# PGTNX05_mainboard.net
KiCad netlist of a schematic drawn in EAGLE
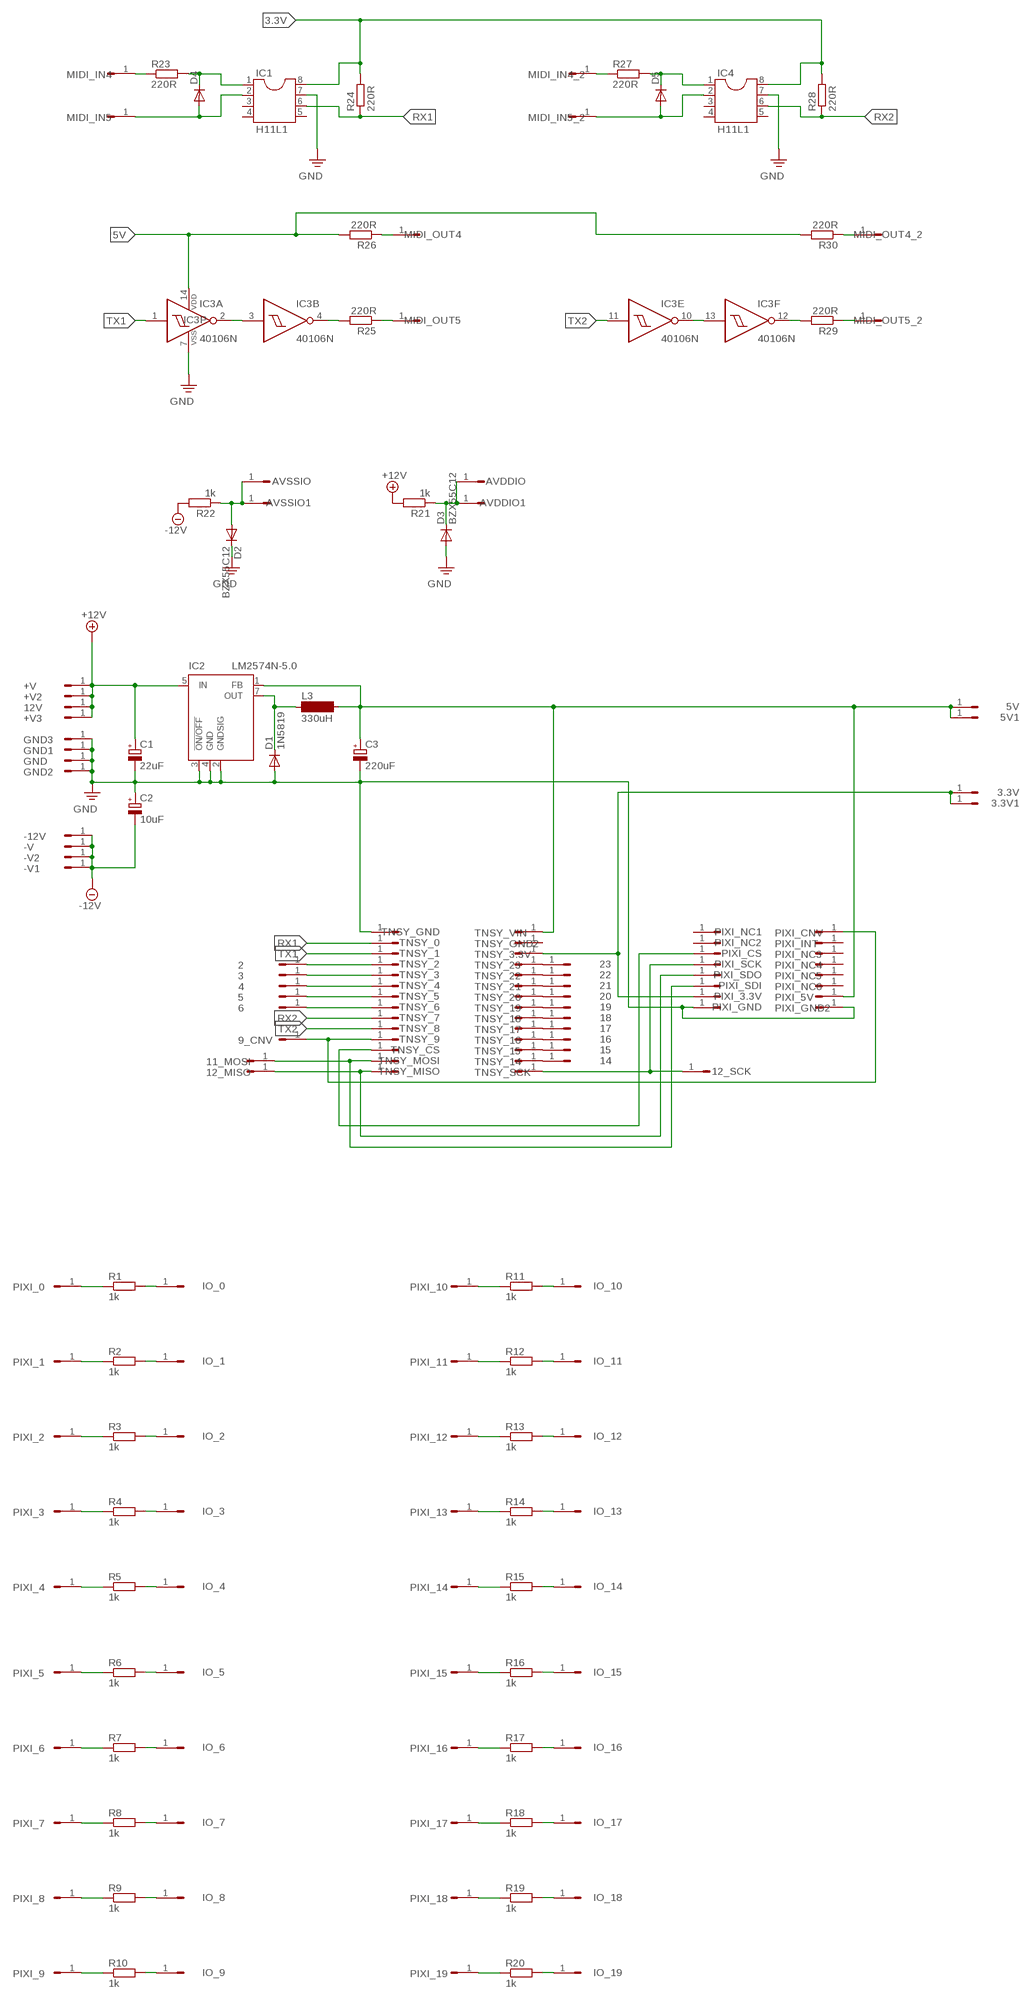
[diagram p0: schematic, sheet 1]

(export (version "E")
  (design (tool "Eeschema 10.0.6"))
  (components
    (comp (ref "+V")
      (value "HEADER/MALE/01")
      (footprint "eagle-import:HEADER_MALE_01")
      (fields (field (name "SPICEPREFIX") "X"))
      (libsource (lib "eagle-import") (part "HEADER/MALE/01"))
    )
    (comp (ref "+V2")
      (value "HEADER/MALE/01")
      (footprint "eagle-import:HEADER_MALE_01")
      (fields (field (name "SPICEPREFIX") "X"))
      (libsource (lib "eagle-import") (part "HEADER/MALE/01"))
    )
    (comp (ref "+V3")
      (value "HEADER/MALE/01")
      (footprint "eagle-import:HEADER_MALE_01")
      (fields (field (name "SPICEPREFIX") "X"))
      (libsource (lib "eagle-import") (part "HEADER/MALE/01"))
    )
    (comp (ref "-12V")
      (value "HEADER/MALE/01")
      (footprint "eagle-import:HEADER_MALE_01")
      (fields (field (name "SPICEPREFIX") "X"))
      (libsource (lib "eagle-import") (part "HEADER/MALE/01"))
    )
    (comp (ref "-V")
      (value "HEADER/MALE/01")
      (footprint "eagle-import:HEADER_MALE_01")
      (fields (field (name "SPICEPREFIX") "X"))
      (libsource (lib "eagle-import") (part "HEADER/MALE/01"))
    )
    (comp (ref "-V1")
      (value "HEADER/MALE/01")
      (footprint "eagle-import:HEADER_MALE_01")
      (fields (field (name "SPICEPREFIX") "X"))
      (libsource (lib "eagle-import") (part "HEADER/MALE/01"))
    )
    (comp (ref "-V2")
      (value "HEADER/MALE/01")
      (footprint "eagle-import:HEADER_MALE_01")
      (fields (field (name "SPICEPREFIX") "X"))
      (libsource (lib "eagle-import") (part "HEADER/MALE/01"))
    )
    (comp (ref "2")
      (value "HEADER/MALE/01")
      (footprint "eagle-import:HEADER_MALE_01")
      (fields (field (name "SPICEPREFIX") "X"))
      (libsource (lib "eagle-import") (part "HEADER/MALE/01"))
    )
    (comp (ref "3")
      (value "HEADER/MALE/01")
      (footprint "eagle-import:HEADER_MALE_01")
      (fields (field (name "SPICEPREFIX") "X"))
      (libsource (lib "eagle-import") (part "HEADER/MALE/01"))
    )
    (comp (ref "3.3V")
      (value "HEADER/MALE/01")
      (footprint "eagle-import:HEADER_MALE_01")
      (fields (field (name "SPICEPREFIX") "X"))
      (libsource (lib "eagle-import") (part "HEADER/MALE/01"))
    )
    (comp (ref "3.3V1")
      (value "HEADER/MALE/01")
      (footprint "eagle-import:HEADER_MALE_01")
      (fields (field (name "SPICEPREFIX") "X"))
      (libsource (lib "eagle-import") (part "HEADER/MALE/01"))
    )
    (comp (ref "4")
      (value "HEADER/MALE/01")
      (footprint "eagle-import:HEADER_MALE_01")
      (fields (field (name "SPICEPREFIX") "X"))
      (libsource (lib "eagle-import") (part "HEADER/MALE/01"))
    )
    (comp (ref "5")
      (value "HEADER/MALE/01")
      (footprint "eagle-import:HEADER_MALE_01")
      (fields (field (name "SPICEPREFIX") "X"))
      (libsource (lib "eagle-import") (part "HEADER/MALE/01"))
    )
    (comp (ref "5V")
      (value "HEADER/MALE/01")
      (footprint "eagle-import:HEADER_MALE_01")
      (fields (field (name "SPICEPREFIX") "X"))
      (libsource (lib "eagle-import") (part "HEADER/MALE/01"))
    )
    (comp (ref "5V1")
      (value "HEADER/MALE/01")
      (footprint "eagle-import:HEADER_MALE_01")
      (fields (field (name "SPICEPREFIX") "X"))
      (libsource (lib "eagle-import") (part "HEADER/MALE/01"))
    )
    (comp (ref "6")
      (value "HEADER/MALE/01")
      (footprint "eagle-import:HEADER_MALE_01")
      (fields (field (name "SPICEPREFIX") "X"))
      (libsource (lib "eagle-import") (part "HEADER/MALE/01"))
    )
    (comp (ref "9_CNV")
      (value "HEADER/MALE/01")
      (footprint "eagle-import:HEADER_MALE_01")
      (fields (field (name "SPICEPREFIX") "X"))
      (libsource (lib "eagle-import") (part "HEADER/MALE/01"))
    )
    (comp (ref "11_MOSI")
      (value "HEADER/MALE/01")
      (footprint "eagle-import:HEADER_MALE_01")
      (fields (field (name "SPICEPREFIX") "X"))
      (libsource (lib "eagle-import") (part "HEADER/MALE/01"))
    )
    (comp (ref "12V")
      (value "HEADER/MALE/01")
      (footprint "eagle-import:HEADER_MALE_01")
      (fields (field (name "SPICEPREFIX") "X"))
      (libsource (lib "eagle-import") (part "HEADER/MALE/01"))
    )
    (comp (ref "12_MISO")
      (value "HEADER/MALE/01")
      (footprint "eagle-import:HEADER_MALE_01")
      (fields (field (name "SPICEPREFIX") "X"))
      (libsource (lib "eagle-import") (part "HEADER/MALE/01"))
    )
    (comp (ref "12_SCK")
      (value "HEADER/MALE/01")
      (footprint "eagle-import:HEADER_MALE_01")
      (fields (field (name "SPICEPREFIX") "X"))
      (libsource (lib "eagle-import") (part "HEADER/MALE/01"))
    )
    (comp (ref "14")
      (value "HEADER/MALE/01")
      (footprint "eagle-import:HEADER_MALE_01")
      (fields (field (name "SPICEPREFIX") "X"))
      (libsource (lib "eagle-import") (part "HEADER/MALE/01"))
    )
    (comp (ref "15")
      (value "HEADER/MALE/01")
      (footprint "eagle-import:HEADER_MALE_01")
      (fields (field (name "SPICEPREFIX") "X"))
      (libsource (lib "eagle-import") (part "HEADER/MALE/01"))
    )
    (comp (ref "16")
      (value "HEADER/MALE/01")
      (footprint "eagle-import:HEADER_MALE_01")
      (fields (field (name "SPICEPREFIX") "X"))
      (libsource (lib "eagle-import") (part "HEADER/MALE/01"))
    )
    (comp (ref "17")
      (value "HEADER/MALE/01")
      (footprint "eagle-import:HEADER_MALE_01")
      (fields (field (name "SPICEPREFIX") "X"))
      (libsource (lib "eagle-import") (part "HEADER/MALE/01"))
    )
    (comp (ref "18")
      (value "HEADER/MALE/01")
      (footprint "eagle-import:HEADER_MALE_01")
      (fields (field (name "SPICEPREFIX") "X"))
      (libsource (lib "eagle-import") (part "HEADER/MALE/01"))
    )
    (comp (ref "19")
      (value "HEADER/MALE/01")
      (footprint "eagle-import:HEADER_MALE_01")
      (fields (field (name "SPICEPREFIX") "X"))
      (libsource (lib "eagle-import") (part "HEADER/MALE/01"))
    )
    (comp (ref "20")
      (value "HEADER/MALE/01")
      (footprint "eagle-import:HEADER_MALE_01")
      (fields (field (name "SPICEPREFIX") "X"))
      (libsource (lib "eagle-import") (part "HEADER/MALE/01"))
    )
    (comp (ref "21")
      (value "HEADER/MALE/01")
      (footprint "eagle-import:HEADER_MALE_01")
      (fields (field (name "SPICEPREFIX") "X"))
      (libsource (lib "eagle-import") (part "HEADER/MALE/01"))
    )
    (comp (ref "22")
      (value "HEADER/MALE/01")
      (footprint "eagle-import:HEADER_MALE_01")
      (fields (field (name "SPICEPREFIX") "X"))
      (libsource (lib "eagle-import") (part "HEADER/MALE/01"))
    )
    (comp (ref "23")
      (value "HEADER/MALE/01")
      (footprint "eagle-import:HEADER_MALE_01")
      (fields (field (name "SPICEPREFIX") "X"))
      (libsource (lib "eagle-import") (part "HEADER/MALE/01"))
    )
    (comp (ref "AVDDIO")
      (value "HEADER/MALE/01")
      (footprint "eagle-import:HEADER_MALE_01")
      (fields (field (name "SPICEPREFIX") "X"))
      (libsource (lib "eagle-import") (part "HEADER/MALE/01"))
    )
    (comp (ref "AVDDIO1")
      (value "HEADER/MALE/01")
      (footprint "eagle-import:HEADER_MALE_01")
      (fields (field (name "SPICEPREFIX") "X"))
      (libsource (lib "eagle-import") (part "HEADER/MALE/01"))
    )
    (comp (ref "AVSSIO")
      (value "HEADER/MALE/01")
      (footprint "eagle-import:HEADER_MALE_01")
      (fields (field (name "SPICEPREFIX") "X"))
      (libsource (lib "eagle-import") (part "HEADER/MALE/01"))
    )
    (comp (ref "AVSSIO1")
      (value "HEADER/MALE/01")
      (footprint "eagle-import:HEADER_MALE_01")
      (fields (field (name "SPICEPREFIX") "X"))
      (libsource (lib "eagle-import") (part "HEADER/MALE/01"))
    )
    (comp (ref "C1")
      (value "22uF")
      (footprint "eagle-import:E5-10,5")
      (fields (field (name "SPICEPREFIX") "C"))
      (libsource (lib "eagle-import") (part "CAPACITOR/POLARIZEDE5-10.5"))
    )
    (comp (ref "C2")
      (value "10uF")
      (footprint "eagle-import:E2,5-6")
      (fields (field (name "SPICEPREFIX") "C"))
      (libsource (lib "eagle-import") (part "CAPACITOR/POLARIZEDE2.5-6"))
    )
    (comp (ref "C3")
      (value "220uF")
      (footprint "eagle-import:E2,5-6")
      (fields (field (name "SPICEPREFIX") "C"))
      (libsource (lib "eagle-import") (part "CAPACITOR/POLARIZEDE2.5-6"))
    )
    (comp (ref "D1")
      (value "1N5819")
      (footprint "eagle-import:DO35-7")
      (libsource (lib "eagle-import") (part "1N4148DO35-7"))
    )
    (comp (ref "D2")
      (value "BZX55C12")
      (footprint "eagle-import:DO35-7")
      (libsource (lib "eagle-import") (part "1N4148DO35-7"))
    )
    (comp (ref "D3")
      (value "BZX55C12")
      (footprint "eagle-import:DO35-7")
      (libsource (lib "eagle-import") (part "1N4148DO35-7"))
    )
    (comp (ref "D4")
      (value "1N4148DO35-7")
      (footprint "eagle-import:DO35-7")
      (libsource (lib "eagle-import") (part "1N4148DO35-7"))
    )
    (comp (ref "D5")
      (value "1N4148DO35-7")
      (footprint "eagle-import:DO35-7")
      (libsource (lib "eagle-import") (part "1N4148DO35-7"))
    )
    (comp (ref "GND")
      (value "HEADER/MALE/01")
      (footprint "eagle-import:HEADER_MALE_01")
      (fields (field (name "SPICEPREFIX") "X"))
      (libsource (lib "eagle-import") (part "HEADER/MALE/01"))
    )
    (comp (ref "GND1")
      (value "HEADER/MALE/01")
      (footprint "eagle-import:HEADER_MALE_01")
      (fields (field (name "SPICEPREFIX") "X"))
      (libsource (lib "eagle-import") (part "HEADER/MALE/01"))
    )
    (comp (ref "GND2")
      (value "HEADER/MALE/01")
      (footprint "eagle-import:HEADER_MALE_01")
      (fields (field (name "SPICEPREFIX") "X"))
      (libsource (lib "eagle-import") (part "HEADER/MALE/01"))
    )
    (comp (ref "GND3")
      (value "HEADER/MALE/01")
      (footprint "eagle-import:HEADER_MALE_01")
      (fields (field (name "SPICEPREFIX") "X"))
      (libsource (lib "eagle-import") (part "HEADER/MALE/01"))
    )
    (comp (ref "IC1")
      (value "H11L1")
      (footprint "eagle-import:DIL08")
      (libsource (lib "eagle-import") (part "DIL8"))
    )
    (comp (ref "IC2")
      (value "LM2574N-5.0")
      (footprint "eagle-import:DIL08")
      (libsource (lib "eagle-import") (part "LM2574?-N5.0"))
    )
    (comp (ref "IC3")
      (value "40106N")
      (footprint "eagle-import:DIL14")
      (libsource (lib "eagle-import") (part "40106N"))
    )
    (comp (ref "IC4")
      (value "H11L1")
      (footprint "eagle-import:DIL08")
      (libsource (lib "eagle-import") (part "DIL8"))
    )
    (comp (ref "IO_0")
      (value "HEADER/MALE/01")
      (footprint "eagle-import:HEADER_MALE_01")
      (fields (field (name "SPICEPREFIX") "X"))
      (libsource (lib "eagle-import") (part "HEADER/MALE/01"))
    )
    (comp (ref "IO_1")
      (value "HEADER/MALE/01")
      (footprint "eagle-import:HEADER_MALE_01")
      (fields (field (name "SPICEPREFIX") "X"))
      (libsource (lib "eagle-import") (part "HEADER/MALE/01"))
    )
    (comp (ref "IO_2")
      (value "HEADER/MALE/01")
      (footprint "eagle-import:HEADER_MALE_01")
      (fields (field (name "SPICEPREFIX") "X"))
      (libsource (lib "eagle-import") (part "HEADER/MALE/01"))
    )
    (comp (ref "IO_3")
      (value "HEADER/MALE/01")
      (footprint "eagle-import:HEADER_MALE_01")
      (fields (field (name "SPICEPREFIX") "X"))
      (libsource (lib "eagle-import") (part "HEADER/MALE/01"))
    )
    (comp (ref "IO_4")
      (value "HEADER/MALE/01")
      (footprint "eagle-import:HEADER_MALE_01")
      (fields (field (name "SPICEPREFIX") "X"))
      (libsource (lib "eagle-import") (part "HEADER/MALE/01"))
    )
    (comp (ref "IO_5")
      (value "HEADER/MALE/01")
      (footprint "eagle-import:HEADER_MALE_01")
      (fields (field (name "SPICEPREFIX") "X"))
      (libsource (lib "eagle-import") (part "HEADER/MALE/01"))
    )
    (comp (ref "IO_6")
      (value "HEADER/MALE/01")
      (footprint "eagle-import:HEADER_MALE_01")
      (fields (field (name "SPICEPREFIX") "X"))
      (libsource (lib "eagle-import") (part "HEADER/MALE/01"))
    )
    (comp (ref "IO_7")
      (value "HEADER/MALE/01")
      (footprint "eagle-import:HEADER_MALE_01")
      (fields (field (name "SPICEPREFIX") "X"))
      (libsource (lib "eagle-import") (part "HEADER/MALE/01"))
    )
    (comp (ref "IO_8")
      (value "HEADER/MALE/01")
      (footprint "eagle-import:HEADER_MALE_01")
      (fields (field (name "SPICEPREFIX") "X"))
      (libsource (lib "eagle-import") (part "HEADER/MALE/01"))
    )
    (comp (ref "IO_9")
      (value "HEADER/MALE/01")
      (footprint "eagle-import:HEADER_MALE_01")
      (fields (field (name "SPICEPREFIX") "X"))
      (libsource (lib "eagle-import") (part "HEADER/MALE/01"))
    )
    (comp (ref "IO_10")
      (value "HEADER/MALE/01")
      (footprint "eagle-import:HEADER_MALE_01")
      (fields (field (name "SPICEPREFIX") "X"))
      (libsource (lib "eagle-import") (part "HEADER/MALE/01"))
    )
    (comp (ref "IO_11")
      (value "HEADER/MALE/01")
      (footprint "eagle-import:HEADER_MALE_01")
      (fields (field (name "SPICEPREFIX") "X"))
      (libsource (lib "eagle-import") (part "HEADER/MALE/01"))
    )
    (comp (ref "IO_12")
      (value "HEADER/MALE/01")
      (footprint "eagle-import:HEADER_MALE_01")
      (fields (field (name "SPICEPREFIX") "X"))
      (libsource (lib "eagle-import") (part "HEADER/MALE/01"))
    )
    (comp (ref "IO_13")
      (value "HEADER/MALE/01")
      (footprint "eagle-import:HEADER_MALE_01")
      (fields (field (name "SPICEPREFIX") "X"))
      (libsource (lib "eagle-import") (part "HEADER/MALE/01"))
    )
    (comp (ref "IO_14")
      (value "HEADER/MALE/01")
      (footprint "eagle-import:HEADER_MALE_01")
      (fields (field (name "SPICEPREFIX") "X"))
      (libsource (lib "eagle-import") (part "HEADER/MALE/01"))
    )
    (comp (ref "IO_15")
      (value "HEADER/MALE/01")
      (footprint "eagle-import:HEADER_MALE_01")
      (fields (field (name "SPICEPREFIX") "X"))
      (libsource (lib "eagle-import") (part "HEADER/MALE/01"))
    )
    (comp (ref "IO_16")
      (value "HEADER/MALE/01")
      (footprint "eagle-import:HEADER_MALE_01")
      (fields (field (name "SPICEPREFIX") "X"))
      (libsource (lib "eagle-import") (part "HEADER/MALE/01"))
    )
    (comp (ref "IO_17")
      (value "HEADER/MALE/01")
      (footprint "eagle-import:HEADER_MALE_01")
      (fields (field (name "SPICEPREFIX") "X"))
      (libsource (lib "eagle-import") (part "HEADER/MALE/01"))
    )
    (comp (ref "IO_18")
      (value "HEADER/MALE/01")
      (footprint "eagle-import:HEADER_MALE_01")
      (fields (field (name "SPICEPREFIX") "X"))
      (libsource (lib "eagle-import") (part "HEADER/MALE/01"))
    )
    (comp (ref "IO_19")
      (value "HEADER/MALE/01")
      (footprint "eagle-import:HEADER_MALE_01")
      (fields (field (name "SPICEPREFIX") "X"))
      (libsource (lib "eagle-import") (part "HEADER/MALE/01"))
    )
    (comp (ref "L3")
      (value "330uH")
      (footprint "eagle-import:BS11")
      (libsource (lib "eagle-import") (part "BS11"))
    )
    (comp (ref "MIDI_IN4")
      (value "HEADER/MALE/01")
      (footprint "eagle-import:HEADER_MALE_01")
      (fields (field (name "SPICEPREFIX") "X"))
      (libsource (lib "eagle-import") (part "HEADER/MALE/01"))
    )
    (comp (ref "MIDI_IN4_2")
      (value "HEADER/MALE/01")
      (footprint "eagle-import:HEADER_MALE_01")
      (fields (field (name "SPICEPREFIX") "X"))
      (libsource (lib "eagle-import") (part "HEADER/MALE/01"))
    )
    (comp (ref "MIDI_IN5")
      (value "HEADER/MALE/01")
      (footprint "eagle-import:HEADER_MALE_01")
      (fields (field (name "SPICEPREFIX") "X"))
      (libsource (lib "eagle-import") (part "HEADER/MALE/01"))
    )
    (comp (ref "MIDI_IN5_2")
      (value "HEADER/MALE/01")
      (footprint "eagle-import:HEADER_MALE_01")
      (fields (field (name "SPICEPREFIX") "X"))
      (libsource (lib "eagle-import") (part "HEADER/MALE/01"))
    )
    (comp (ref "MIDI_OUT4")
      (value "HEADER/MALE/01")
      (footprint "eagle-import:HEADER_MALE_01")
      (fields (field (name "SPICEPREFIX") "X"))
      (libsource (lib "eagle-import") (part "HEADER/MALE/01"))
    )
    (comp (ref "MIDI_OUT4_2")
      (value "HEADER/MALE/01")
      (footprint "eagle-import:HEADER_MALE_01")
      (fields (field (name "SPICEPREFIX") "X"))
      (libsource (lib "eagle-import") (part "HEADER/MALE/01"))
    )
    (comp (ref "MIDI_OUT5")
      (value "HEADER/MALE/01")
      (footprint "eagle-import:HEADER_MALE_01")
      (fields (field (name "SPICEPREFIX") "X"))
      (libsource (lib "eagle-import") (part "HEADER/MALE/01"))
    )
    (comp (ref "MIDI_OUT5_2")
      (value "HEADER/MALE/01")
      (footprint "eagle-import:HEADER_MALE_01")
      (fields (field (name "SPICEPREFIX") "X"))
      (libsource (lib "eagle-import") (part "HEADER/MALE/01"))
    )
    (comp (ref "PIXI_0")
      (value "HEADER/MALE/01")
      (footprint "eagle-import:HEADER_MALE_01")
      (fields (field (name "SPICEPREFIX") "X"))
      (libsource (lib "eagle-import") (part "HEADER/MALE/01"))
    )
    (comp (ref "PIXI_1")
      (value "HEADER/MALE/01")
      (footprint "eagle-import:HEADER_MALE_01")
      (fields (field (name "SPICEPREFIX") "X"))
      (libsource (lib "eagle-import") (part "HEADER/MALE/01"))
    )
    (comp (ref "PIXI_2")
      (value "HEADER/MALE/01")
      (footprint "eagle-import:HEADER_MALE_01")
      (fields (field (name "SPICEPREFIX") "X"))
      (libsource (lib "eagle-import") (part "HEADER/MALE/01"))
    )
    (comp (ref "PIXI_3")
      (value "HEADER/MALE/01")
      (footprint "eagle-import:HEADER_MALE_01")
      (fields (field (name "SPICEPREFIX") "X"))
      (libsource (lib "eagle-import") (part "HEADER/MALE/01"))
    )
    (comp (ref "PIXI_3.3V")
      (value "HEADER/MALE/01")
      (footprint "eagle-import:HEADER_MALE_01")
      (fields (field (name "SPICEPREFIX") "X"))
      (libsource (lib "eagle-import") (part "HEADER/MALE/01"))
    )
    (comp (ref "PIXI_4")
      (value "HEADER/MALE/01")
      (footprint "eagle-import:HEADER_MALE_01")
      (fields (field (name "SPICEPREFIX") "X"))
      (libsource (lib "eagle-import") (part "HEADER/MALE/01"))
    )
    (comp (ref "PIXI_5")
      (value "HEADER/MALE/01")
      (footprint "eagle-import:HEADER_MALE_01")
      (fields (field (name "SPICEPREFIX") "X"))
      (libsource (lib "eagle-import") (part "HEADER/MALE/01"))
    )
    (comp (ref "PIXI_5V")
      (value "HEADER/MALE/01")
      (footprint "eagle-import:HEADER_MALE_01")
      (fields (field (name "SPICEPREFIX") "X"))
      (libsource (lib "eagle-import") (part "HEADER/MALE/01"))
    )
    (comp (ref "PIXI_6")
      (value "HEADER/MALE/01")
      (footprint "eagle-import:HEADER_MALE_01")
      (fields (field (name "SPICEPREFIX") "X"))
      (libsource (lib "eagle-import") (part "HEADER/MALE/01"))
    )
    (comp (ref "PIXI_7")
      (value "HEADER/MALE/01")
      (footprint "eagle-import:HEADER_MALE_01")
      (fields (field (name "SPICEPREFIX") "X"))
      (libsource (lib "eagle-import") (part "HEADER/MALE/01"))
    )
    (comp (ref "PIXI_8")
      (value "HEADER/MALE/01")
      (footprint "eagle-import:HEADER_MALE_01")
      (fields (field (name "SPICEPREFIX") "X"))
      (libsource (lib "eagle-import") (part "HEADER/MALE/01"))
    )
    (comp (ref "PIXI_9")
      (value "HEADER/MALE/01")
      (footprint "eagle-import:HEADER_MALE_01")
      (fields (field (name "SPICEPREFIX") "X"))
      (libsource (lib "eagle-import") (part "HEADER/MALE/01"))
    )
    (comp (ref "PIXI_10")
      (value "HEADER/MALE/01")
      (footprint "eagle-import:HEADER_MALE_01")
      (fields (field (name "SPICEPREFIX") "X"))
      (libsource (lib "eagle-import") (part "HEADER/MALE/01"))
    )
    (comp (ref "PIXI_11")
      (value "HEADER/MALE/01")
      (footprint "eagle-import:HEADER_MALE_01")
      (fields (field (name "SPICEPREFIX") "X"))
      (libsource (lib "eagle-import") (part "HEADER/MALE/01"))
    )
    (comp (ref "PIXI_12")
      (value "HEADER/MALE/01")
      (footprint "eagle-import:HEADER_MALE_01")
      (fields (field (name "SPICEPREFIX") "X"))
      (libsource (lib "eagle-import") (part "HEADER/MALE/01"))
    )
    (comp (ref "PIXI_13")
      (value "HEADER/MALE/01")
      (footprint "eagle-import:HEADER_MALE_01")
      (fields (field (name "SPICEPREFIX") "X"))
      (libsource (lib "eagle-import") (part "HEADER/MALE/01"))
    )
    (comp (ref "PIXI_14")
      (value "HEADER/MALE/01")
      (footprint "eagle-import:HEADER_MALE_01")
      (fields (field (name "SPICEPREFIX") "X"))
      (libsource (lib "eagle-import") (part "HEADER/MALE/01"))
    )
    (comp (ref "PIXI_15")
      (value "HEADER/MALE/01")
      (footprint "eagle-import:HEADER_MALE_01")
      (fields (field (name "SPICEPREFIX") "X"))
      (libsource (lib "eagle-import") (part "HEADER/MALE/01"))
    )
    (comp (ref "PIXI_16")
      (value "HEADER/MALE/01")
      (footprint "eagle-import:HEADER_MALE_01")
      (fields (field (name "SPICEPREFIX") "X"))
      (libsource (lib "eagle-import") (part "HEADER/MALE/01"))
    )
    (comp (ref "PIXI_17")
      (value "HEADER/MALE/01")
      (footprint "eagle-import:HEADER_MALE_01")
      (fields (field (name "SPICEPREFIX") "X"))
      (libsource (lib "eagle-import") (part "HEADER/MALE/01"))
    )
    (comp (ref "PIXI_18")
      (value "HEADER/MALE/01")
      (footprint "eagle-import:HEADER_MALE_01")
      (fields (field (name "SPICEPREFIX") "X"))
      (libsource (lib "eagle-import") (part "HEADER/MALE/01"))
    )
    (comp (ref "PIXI_19")
      (value "HEADER/MALE/01")
      (footprint "eagle-import:HEADER_MALE_01")
      (fields (field (name "SPICEPREFIX") "X"))
      (libsource (lib "eagle-import") (part "HEADER/MALE/01"))
    )
    (comp (ref "PIXI_CNV")
      (value "HEADER/MALE/01")
      (footprint "eagle-import:HEADER_MALE_01")
      (fields (field (name "SPICEPREFIX") "X"))
      (libsource (lib "eagle-import") (part "HEADER/MALE/01"))
    )
    (comp (ref "PIXI_CS")
      (value "HEADER/MALE/01")
      (footprint "eagle-import:HEADER_MALE_01")
      (fields (field (name "SPICEPREFIX") "X"))
      (libsource (lib "eagle-import") (part "HEADER/MALE/01"))
    )
    (comp (ref "PIXI_GND")
      (value "HEADER/MALE/01")
      (footprint "eagle-import:HEADER_MALE_01")
      (fields (field (name "SPICEPREFIX") "X"))
      (libsource (lib "eagle-import") (part "HEADER/MALE/01"))
    )
    (comp (ref "PIXI_GND2")
      (value "HEADER/MALE/01")
      (footprint "eagle-import:HEADER_MALE_01")
      (fields (field (name "SPICEPREFIX") "X"))
      (libsource (lib "eagle-import") (part "HEADER/MALE/01"))
    )
    (comp (ref "PIXI_INT")
      (value "HEADER/MALE/01")
      (footprint "eagle-import:HEADER_MALE_01")
      (fields (field (name "SPICEPREFIX") "X"))
      (libsource (lib "eagle-import") (part "HEADER/MALE/01"))
    )
    (comp (ref "PIXI_NC1")
      (value "HEADER/MALE/01")
      (footprint "eagle-import:HEADER_MALE_01")
      (fields (field (name "SPICEPREFIX") "X"))
      (libsource (lib "eagle-import") (part "HEADER/MALE/01"))
    )
    (comp (ref "PIXI_NC2")
      (value "HEADER/MALE/01")
      (footprint "eagle-import:HEADER_MALE_01")
      (fields (field (name "SPICEPREFIX") "X"))
      (libsource (lib "eagle-import") (part "HEADER/MALE/01"))
    )
    (comp (ref "PIXI_NC3")
      (value "HEADER/MALE/01")
      (footprint "eagle-import:HEADER_MALE_01")
      (fields (field (name "SPICEPREFIX") "X"))
      (libsource (lib "eagle-import") (part "HEADER/MALE/01"))
    )
    (comp (ref "PIXI_NC4")
      (value "HEADER/MALE/01")
      (footprint "eagle-import:HEADER_MALE_01")
      (fields (field (name "SPICEPREFIX") "X"))
      (libsource (lib "eagle-import") (part "HEADER/MALE/01"))
    )
    (comp (ref "PIXI_NC5")
      (value "HEADER/MALE/01")
      (footprint "eagle-import:HEADER_MALE_01")
      (fields (field (name "SPICEPREFIX") "X"))
      (libsource (lib "eagle-import") (part "HEADER/MALE/01"))
    )
    (comp (ref "PIXI_NC6")
      (value "HEADER/MALE/01")
      (footprint "eagle-import:HEADER_MALE_01")
      (fields (field (name "SPICEPREFIX") "X"))
      (libsource (lib "eagle-import") (part "HEADER/MALE/01"))
    )
    (comp (ref "PIXI_SCK")
      (value "HEADER/MALE/01")
      (footprint "eagle-import:HEADER_MALE_01")
      (fields (field (name "SPICEPREFIX") "X"))
      (libsource (lib "eagle-import") (part "HEADER/MALE/01"))
    )
    (comp (ref "PIXI_SDI")
      (value "HEADER/MALE/01")
      (footprint "eagle-import:HEADER_MALE_01")
      (fields (field (name "SPICEPREFIX") "X"))
      (libsource (lib "eagle-import") (part "HEADER/MALE/01"))
    )
    (comp (ref "PIXI_SDO")
      (value "HEADER/MALE/01")
      (footprint "eagle-import:HEADER_MALE_01")
      (fields (field (name "SPICEPREFIX") "X"))
      (libsource (lib "eagle-import") (part "HEADER/MALE/01"))
    )
    (comp (ref "R1")
      (value "1k")
      (footprint "eagle-import:RESISTOR_7.5")
      (libsource (lib "eagle-import") (part "RESISTORRESISTOR/UPRIGHT/7.5"))
    )
    (comp (ref "R2")
      (value "1k")
      (footprint "eagle-import:RESISTOR_7.5")
      (libsource (lib "eagle-import") (part "RESISTORRESISTOR/UPRIGHT/7.5"))
    )
    (comp (ref "R3")
      (value "1k")
      (footprint "eagle-import:RESISTOR_7.5")
      (libsource (lib "eagle-import") (part "RESISTORRESISTOR/UPRIGHT/7.5"))
    )
    (comp (ref "R4")
      (value "1k")
      (footprint "eagle-import:RESISTOR_7.5")
      (libsource (lib "eagle-import") (part "RESISTORRESISTOR/UPRIGHT/7.5"))
    )
    (comp (ref "R5")
      (value "1k")
      (footprint "eagle-import:RESISTOR_7.5")
      (libsource (lib "eagle-import") (part "RESISTORRESISTOR/UPRIGHT/7.5"))
    )
    (comp (ref "R6")
      (value "1k")
      (footprint "eagle-import:RESISTOR_7.5")
      (libsource (lib "eagle-import") (part "RESISTORRESISTOR/UPRIGHT/7.5"))
    )
    (comp (ref "R7")
      (value "1k")
      (footprint "eagle-import:RESISTOR_7.5")
      (libsource (lib "eagle-import") (part "RESISTORRESISTOR/UPRIGHT/7.5"))
    )
    (comp (ref "R8")
      (value "1k")
      (footprint "eagle-import:RESISTOR_7.5")
      (libsource (lib "eagle-import") (part "RESISTORRESISTOR/UPRIGHT/7.5"))
    )
    (comp (ref "R9")
      (value "1k")
      (footprint "eagle-import:RESISTOR_7.5")
      (libsource (lib "eagle-import") (part "RESISTORRESISTOR/UPRIGHT/7.5"))
    )
    (comp (ref "R10")
      (value "1k")
      (footprint "eagle-import:RESISTOR_7.5")
      (libsource (lib "eagle-import") (part "RESISTORRESISTOR/UPRIGHT/7.5"))
    )
    (comp (ref "R11")
      (value "1k")
      (footprint "eagle-import:RESISTOR_7.5")
      (libsource (lib "eagle-import") (part "RESISTORRESISTOR/UPRIGHT/7.5"))
    )
    (comp (ref "R12")
      (value "1k")
      (footprint "eagle-import:RESISTOR_7.5")
      (libsource (lib "eagle-import") (part "RESISTORRESISTOR/UPRIGHT/7.5"))
    )
    (comp (ref "R13")
      (value "1k")
      (footprint "eagle-import:RESISTOR_7.5")
      (libsource (lib "eagle-import") (part "RESISTORRESISTOR/UPRIGHT/7.5"))
    )
    (comp (ref "R14")
      (value "1k")
      (footprint "eagle-import:RESISTOR_7.5")
      (libsource (lib "eagle-import") (part "RESISTORRESISTOR/UPRIGHT/7.5"))
    )
    (comp (ref "R15")
      (value "1k")
      (footprint "eagle-import:RESISTOR_7.5")
      (libsource (lib "eagle-import") (part "RESISTORRESISTOR/UPRIGHT/7.5"))
    )
    (comp (ref "R16")
      (value "1k")
      (footprint "eagle-import:RESISTOR_7.5")
      (libsource (lib "eagle-import") (part "RESISTORRESISTOR/UPRIGHT/7.5"))
    )
    (comp (ref "R17")
      (value "1k")
      (footprint "eagle-import:RESISTOR_7.5")
      (libsource (lib "eagle-import") (part "RESISTORRESISTOR/UPRIGHT/7.5"))
    )
    (comp (ref "R18")
      (value "1k")
      (footprint "eagle-import:RESISTOR_7.5")
      (libsource (lib "eagle-import") (part "RESISTORRESISTOR/UPRIGHT/7.5"))
    )
    (comp (ref "R19")
      (value "1k")
      (footprint "eagle-import:RESISTOR_7.5")
      (libsource (lib "eagle-import") (part "RESISTORRESISTOR/UPRIGHT/7.5"))
    )
    (comp (ref "R20")
      (value "1k")
      (footprint "eagle-import:RESISTOR_7.5")
      (libsource (lib "eagle-import") (part "RESISTORRESISTOR/UPRIGHT/7.5"))
    )
    (comp (ref "R21")
      (value "1k")
      (footprint "eagle-import:RESISTOR_7.5")
      (libsource (lib "eagle-import") (part "RESISTORRESISTOR/UPRIGHT/7.5"))
    )
    (comp (ref "R22")
      (value "1k")
      (footprint "eagle-import:RESISTOR_7.5")
      (libsource (lib "eagle-import") (part "RESISTORRESISTOR/UPRIGHT/7.5"))
    )
    (comp (ref "R23")
      (value "220R")
      (footprint "eagle-import:RESISTOR_7.5")
      (libsource (lib "eagle-import") (part "RESISTORRESISTOR/UPRIGHT/7.5"))
    )
    (comp (ref "R24")
      (value "220R")
      (footprint "eagle-import:RESISTOR_7.5")
      (libsource (lib "eagle-import") (part "RESISTORRESISTOR/UPRIGHT/7.5"))
    )
    (comp (ref "R25")
      (value "220R")
      (footprint "eagle-import:RESISTOR_7.5")
      (libsource (lib "eagle-import") (part "RESISTORRESISTOR/UPRIGHT/7.5"))
    )
    (comp (ref "R26")
      (value "220R")
      (footprint "eagle-import:RESISTOR_7.5")
      (libsource (lib "eagle-import") (part "RESISTORRESISTOR/UPRIGHT/7.5"))
    )
    (comp (ref "R27")
      (value "220R")
      (footprint "eagle-import:RESISTOR_7.5")
      (libsource (lib "eagle-import") (part "RESISTORRESISTOR/UPRIGHT/7.5"))
    )
    (comp (ref "R28")
      (value "220R")
      (footprint "eagle-import:RESISTOR_7.5")
      (libsource (lib "eagle-import") (part "RESISTORRESISTOR/UPRIGHT/7.5"))
    )
    (comp (ref "R29")
      (value "220R")
      (footprint "eagle-import:RESISTOR_7.5")
      (libsource (lib "eagle-import") (part "RESISTORRESISTOR/UPRIGHT/7.5"))
    )
    (comp (ref "R30")
      (value "220R")
      (footprint "eagle-import:RESISTOR_7.5")
      (libsource (lib "eagle-import") (part "RESISTORRESISTOR/UPRIGHT/7.5"))
    )
    (comp (ref "TNSY_0")
      (value "HEADER/MALE/01")
      (footprint "eagle-import:HEADER_MALE_01")
      (fields (field (name "SPICEPREFIX") "X"))
      (libsource (lib "eagle-import") (part "HEADER/MALE/01"))
    )
    (comp (ref "TNSY_1")
      (value "HEADER/MALE/01")
      (footprint "eagle-import:HEADER_MALE_01")
      (fields (field (name "SPICEPREFIX") "X"))
      (libsource (lib "eagle-import") (part "HEADER/MALE/01"))
    )
    (comp (ref "TNSY_2")
      (value "HEADER/MALE/01")
      (footprint "eagle-import:HEADER_MALE_01")
      (fields (field (name "SPICEPREFIX") "X"))
      (libsource (lib "eagle-import") (part "HEADER/MALE/01"))
    )
    (comp (ref "TNSY_3")
      (value "HEADER/MALE/01")
      (footprint "eagle-import:HEADER_MALE_01")
      (fields (field (name "SPICEPREFIX") "X"))
      (libsource (lib "eagle-import") (part "HEADER/MALE/01"))
    )
    (comp (ref "TNSY_3.3V")
      (value "HEADER/MALE/01")
      (footprint "eagle-import:HEADER_MALE_01")
      (fields (field (name "SPICEPREFIX") "X"))
      (libsource (lib "eagle-import") (part "HEADER/MALE/01"))
    )
    (comp (ref "TNSY_4")
      (value "HEADER/MALE/01")
      (footprint "eagle-import:HEADER_MALE_01")
      (fields (field (name "SPICEPREFIX") "X"))
      (libsource (lib "eagle-import") (part "HEADER/MALE/01"))
    )
    (comp (ref "TNSY_5")
      (value "HEADER/MALE/01")
      (footprint "eagle-import:HEADER_MALE_01")
      (fields (field (name "SPICEPREFIX") "X"))
      (libsource (lib "eagle-import") (part "HEADER/MALE/01"))
    )
    (comp (ref "TNSY_6")
      (value "HEADER/MALE/01")
      (footprint "eagle-import:HEADER_MALE_01")
      (fields (field (name "SPICEPREFIX") "X"))
      (libsource (lib "eagle-import") (part "HEADER/MALE/01"))
    )
    (comp (ref "TNSY_7")
      (value "HEADER/MALE/01")
      (footprint "eagle-import:HEADER_MALE_01")
      (fields (field (name "SPICEPREFIX") "X"))
      (libsource (lib "eagle-import") (part "HEADER/MALE/01"))
    )
    (comp (ref "TNSY_8")
      (value "HEADER/MALE/01")
      (footprint "eagle-import:HEADER_MALE_01")
      (fields (field (name "SPICEPREFIX") "X"))
      (libsource (lib "eagle-import") (part "HEADER/MALE/01"))
    )
    (comp (ref "TNSY_9")
      (value "HEADER/MALE/01")
      (footprint "eagle-import:HEADER_MALE_01")
      (fields (field (name "SPICEPREFIX") "X"))
      (libsource (lib "eagle-import") (part "HEADER/MALE/01"))
    )
    (comp (ref "TNSY_14")
      (value "HEADER/MALE/01")
      (footprint "eagle-import:HEADER_MALE_01")
      (fields (field (name "SPICEPREFIX") "X"))
      (libsource (lib "eagle-import") (part "HEADER/MALE/01"))
    )
    (comp (ref "TNSY_15")
      (value "HEADER/MALE/01")
      (footprint "eagle-import:HEADER_MALE_01")
      (fields (field (name "SPICEPREFIX") "X"))
      (libsource (lib "eagle-import") (part "HEADER/MALE/01"))
    )
    (comp (ref "TNSY_16")
      (value "HEADER/MALE/01")
      (footprint "eagle-import:HEADER_MALE_01")
      (fields (field (name "SPICEPREFIX") "X"))
      (libsource (lib "eagle-import") (part "HEADER/MALE/01"))
    )
    (comp (ref "TNSY_17")
      (value "HEADER/MALE/01")
      (footprint "eagle-import:HEADER_MALE_01")
      (fields (field (name "SPICEPREFIX") "X"))
      (libsource (lib "eagle-import") (part "HEADER/MALE/01"))
    )
    (comp (ref "TNSY_18")
      (value "HEADER/MALE/01")
      (footprint "eagle-import:HEADER_MALE_01")
      (fields (field (name "SPICEPREFIX") "X"))
      (libsource (lib "eagle-import") (part "HEADER/MALE/01"))
    )
    (comp (ref "TNSY_19")
      (value "HEADER/MALE/01")
      (footprint "eagle-import:HEADER_MALE_01")
      (fields (field (name "SPICEPREFIX") "X"))
      (libsource (lib "eagle-import") (part "HEADER/MALE/01"))
    )
    (comp (ref "TNSY_20")
      (value "HEADER/MALE/01")
      (footprint "eagle-import:HEADER_MALE_01")
      (fields (field (name "SPICEPREFIX") "X"))
      (libsource (lib "eagle-import") (part "HEADER/MALE/01"))
    )
    (comp (ref "TNSY_21")
      (value "HEADER/MALE/01")
      (footprint "eagle-import:HEADER_MALE_01")
      (fields (field (name "SPICEPREFIX") "X"))
      (libsource (lib "eagle-import") (part "HEADER/MALE/01"))
    )
    (comp (ref "TNSY_22")
      (value "HEADER/MALE/01")
      (footprint "eagle-import:HEADER_MALE_01")
      (fields (field (name "SPICEPREFIX") "X"))
      (libsource (lib "eagle-import") (part "HEADER/MALE/01"))
    )
    (comp (ref "TNSY_23")
      (value "HEADER/MALE/01")
      (footprint "eagle-import:HEADER_MALE_01")
      (fields (field (name "SPICEPREFIX") "X"))
      (libsource (lib "eagle-import") (part "HEADER/MALE/01"))
    )
    (comp (ref "TNSY_CS")
      (value "HEADER/MALE/01")
      (footprint "eagle-import:HEADER_MALE_01")
      (fields (field (name "SPICEPREFIX") "X"))
      (libsource (lib "eagle-import") (part "HEADER/MALE/01"))
    )
    (comp (ref "TNSY_GND")
      (value "HEADER/MALE/01")
      (footprint "eagle-import:HEADER_MALE_01")
      (fields (field (name "SPICEPREFIX") "X"))
      (libsource (lib "eagle-import") (part "HEADER/MALE/01"))
    )
    (comp (ref "TNSY_GND2")
      (value "HEADER/MALE/01")
      (footprint "eagle-import:HEADER_MALE_01")
      (fields (field (name "SPICEPREFIX") "X"))
      (libsource (lib "eagle-import") (part "HEADER/MALE/01"))
    )
    (comp (ref "TNSY_MISO")
      (value "HEADER/MALE/01")
      (footprint "eagle-import:HEADER_MALE_01")
      (fields (field (name "SPICEPREFIX") "X"))
      (libsource (lib "eagle-import") (part "HEADER/MALE/01"))
    )
    (comp (ref "TNSY_MOSI")
      (value "HEADER/MALE/01")
      (footprint "eagle-import:HEADER_MALE_01")
      (fields (field (name "SPICEPREFIX") "X"))
      (libsource (lib "eagle-import") (part "HEADER/MALE/01"))
    )
    (comp (ref "TNSY_SCK")
      (value "HEADER/MALE/01")
      (footprint "eagle-import:HEADER_MALE_01")
      (fields (field (name "SPICEPREFIX") "X"))
      (libsource (lib "eagle-import") (part "HEADER/MALE/01"))
    )
    (comp (ref "TNSY_VIN")
      (value "HEADER/MALE/01")
      (footprint "eagle-import:HEADER_MALE_01")
      (fields (field (name "SPICEPREFIX") "X"))
      (libsource (lib "eagle-import") (part "HEADER/MALE/01"))
    )
  )
  (nets
    (net (code "1") (name "+12V") (class "Default")
      (node (ref "+V") (pin "1") (pinfunction "3_1") (pintype "passive"))
      (node (ref "+V2") (pin "1") (pinfunction "3_1") (pintype "passive"))
      (node (ref "+V3") (pin "1") (pinfunction "3_1") (pintype "passive"))
      (node (ref "12V") (pin "1") (pinfunction "3_1") (pintype "passive"))
      (node (ref "C1") (pin "+") (pinfunction "+_+") (pintype "passive"))
      (node (ref "IC2") (pin "5") (pinfunction "IN_5") (pintype "input"))
      (node (ref "R21") (pin "2") (pinfunction "2_2") (pintype "passive"))
    )
    (net (code "2") (name "-12V") (class "Default")
      (node (ref "-12V") (pin "1") (pinfunction "3_1") (pintype "passive"))
      (node (ref "-V") (pin "1") (pinfunction "3_1") (pintype "passive"))
      (node (ref "-V1") (pin "1") (pinfunction "3_1") (pintype "passive"))
      (node (ref "-V2") (pin "1") (pinfunction "3_1") (pintype "passive"))
      (node (ref "C2") (pin "-") (pinfunction "-_-") (pintype "passive"))
      (node (ref "R22") (pin "2") (pinfunction "2_2") (pintype "passive"))
    )
    (net (code "3") (name "3.3V") (class "Default")
      (node (ref "3.3V") (pin "1") (pinfunction "3_1") (pintype "passive"))
      (node (ref "3.3V1") (pin "1") (pinfunction "3_1") (pintype "passive"))
      (node (ref "IC1") (pin "8") (pinfunction "8_8") (pintype "passive"))
      (node (ref "IC4") (pin "8") (pinfunction "8_8") (pintype "passive"))
      (node (ref "PIXI_3.3V") (pin "1") (pinfunction "3_1") (pintype "passive"))
      (node (ref "R24") (pin "2") (pinfunction "2_2") (pintype "passive"))
      (node (ref "R28") (pin "2") (pinfunction "2_2") (pintype "passive"))
      (node (ref "TNSY_3.3V") (pin "1") (pinfunction "3_1") (pintype "passive"))
    )
    (net (code "4") (name "5V") (class "Default")
      (node (ref "5V") (pin "1") (pinfunction "3_1") (pintype "passive"))
      (node (ref "5V1") (pin "1") (pinfunction "3_1") (pintype "passive"))
      (node (ref "C3") (pin "+") (pinfunction "+_+") (pintype "passive"))
      (node (ref "IC2") (pin "1") (pinfunction "FB_1") (pintype "input"))
      (node (ref "IC3") (pin "14") (pinfunction "VDD_14") (pintype "power_in"))
      (node (ref "L3") (pin "2") (pinfunction "2_2") (pintype "passive"))
      (node (ref "PIXI_5V") (pin "1") (pinfunction "3_1") (pintype "passive"))
      (node (ref "R26") (pin "2") (pinfunction "2_2") (pintype "passive"))
      (node (ref "R30") (pin "2") (pinfunction "2_2") (pintype "passive"))
      (node (ref "TNSY_VIN") (pin "1") (pinfunction "3_1") (pintype "passive"))
    )
    (net (code "5") (name "GND") (class "Default")
      (node (ref "C1") (pin "-") (pinfunction "-_-") (pintype "passive"))
      (node (ref "C2") (pin "+") (pinfunction "+_+") (pintype "passive"))
      (node (ref "C3") (pin "-") (pinfunction "-_-") (pintype "passive"))
      (node (ref "D1") (pin "A") (pinfunction "A_A") (pintype "passive"))
      (node (ref "D2") (pin "C") (pinfunction "C_C") (pintype "passive"))
      (node (ref "D3") (pin "A") (pinfunction "A_A") (pintype "passive"))
      (node (ref "GND") (pin "1") (pinfunction "3_1") (pintype "passive"))
      (node (ref "GND1") (pin "1") (pinfunction "3_1") (pintype "passive"))
      (node (ref "GND2") (pin "1") (pinfunction "3_1") (pintype "passive"))
      (node (ref "GND3") (pin "1") (pinfunction "3_1") (pintype "passive"))
      (node (ref "IC1") (pin "7") (pinfunction "7_7") (pintype "passive"))
      (node (ref "IC2") (pin "2") (pinfunction "GNDSIG_2") (pintype "input"))
      (node (ref "IC2") (pin "3") (pinfunction "~{ON/OFF}_3") (pintype "input"))
      (node (ref "IC2") (pin "4") (pinfunction "GND_4") (pintype "power_in"))
      (node (ref "IC3") (pin "7") (pinfunction "VSS_7") (pintype "power_in"))
      (node (ref "IC4") (pin "7") (pinfunction "7_7") (pintype "passive"))
      (node (ref "PIXI_GND") (pin "1") (pinfunction "3_1") (pintype "passive"))
      (node (ref "PIXI_GND2") (pin "1") (pinfunction "3_1") (pintype "passive"))
      (node (ref "TNSY_GND") (pin "1") (pinfunction "3_1") (pintype "passive"))
    )
    (net (code "6") (name "Net-(2-3)") (class "Default")
      (node (ref "2") (pin "1") (pinfunction "3_1") (pintype "passive"))
      (node (ref "TNSY_2") (pin "1") (pinfunction "3_1") (pintype "passive"))
    )
    (net (code "7") (name "Net-(3-3)") (class "Default")
      (node (ref "3") (pin "1") (pinfunction "3_1") (pintype "passive"))
      (node (ref "TNSY_3") (pin "1") (pinfunction "3_1") (pintype "passive"))
    )
    (net (code "8") (name "Net-(4-3)") (class "Default")
      (node (ref "4") (pin "1") (pinfunction "3_1") (pintype "passive"))
      (node (ref "TNSY_4") (pin "1") (pinfunction "3_1") (pintype "passive"))
    )
    (net (code "9") (name "Net-(5-3)") (class "Default")
      (node (ref "5") (pin "1") (pinfunction "3_1") (pintype "passive"))
      (node (ref "TNSY_5") (pin "1") (pinfunction "3_1") (pintype "passive"))
    )
    (net (code "10") (name "Net-(6-3)") (class "Default")
      (node (ref "6") (pin "1") (pinfunction "3_1") (pintype "passive"))
      (node (ref "TNSY_6") (pin "1") (pinfunction "3_1") (pintype "passive"))
    )
    (net (code "11") (name "Net-(9_CNV-3)") (class "Default")
      (node (ref "9_CNV") (pin "1") (pinfunction "3_1") (pintype "passive"))
      (node (ref "PIXI_CNV") (pin "1") (pinfunction "3_1") (pintype "passive"))
      (node (ref "TNSY_9") (pin "1") (pinfunction "3_1") (pintype "passive"))
    )
    (net (code "12") (name "Net-(11_MOSI-3)") (class "Default")
      (node (ref "11_MOSI") (pin "1") (pinfunction "3_1") (pintype "passive"))
      (node (ref "PIXI_SDI") (pin "1") (pinfunction "3_1") (pintype "passive"))
      (node (ref "TNSY_MOSI") (pin "1") (pinfunction "3_1") (pintype "passive"))
    )
    (net (code "13") (name "Net-(12_MISO-3)") (class "Default")
      (node (ref "12_MISO") (pin "1") (pinfunction "3_1") (pintype "passive"))
      (node (ref "PIXI_SDO") (pin "1") (pinfunction "3_1") (pintype "passive"))
      (node (ref "TNSY_MISO") (pin "1") (pinfunction "3_1") (pintype "passive"))
    )
    (net (code "14") (name "Net-(12_SCK-3)") (class "Default")
      (node (ref "12_SCK") (pin "1") (pinfunction "3_1") (pintype "passive"))
      (node (ref "PIXI_SCK") (pin "1") (pinfunction "3_1") (pintype "passive"))
      (node (ref "TNSY_SCK") (pin "1") (pinfunction "3_1") (pintype "passive"))
    )
    (net (code "15") (name "Net-(14-3)") (class "Default")
      (node (ref "14") (pin "1") (pinfunction "3_1") (pintype "passive"))
      (node (ref "TNSY_14") (pin "1") (pinfunction "3_1") (pintype "passive"))
    )
    (net (code "16") (name "Net-(15-3)") (class "Default")
      (node (ref "15") (pin "1") (pinfunction "3_1") (pintype "passive"))
      (node (ref "TNSY_15") (pin "1") (pinfunction "3_1") (pintype "passive"))
    )
    (net (code "17") (name "Net-(16-3)") (class "Default")
      (node (ref "16") (pin "1") (pinfunction "3_1") (pintype "passive"))
      (node (ref "TNSY_16") (pin "1") (pinfunction "3_1") (pintype "passive"))
    )
    (net (code "18") (name "Net-(17-3)") (class "Default")
      (node (ref "17") (pin "1") (pinfunction "3_1") (pintype "passive"))
      (node (ref "TNSY_17") (pin "1") (pinfunction "3_1") (pintype "passive"))
    )
    (net (code "19") (name "Net-(18-3)") (class "Default")
      (node (ref "18") (pin "1") (pinfunction "3_1") (pintype "passive"))
      (node (ref "TNSY_18") (pin "1") (pinfunction "3_1") (pintype "passive"))
    )
    (net (code "20") (name "Net-(19-3)") (class "Default")
      (node (ref "19") (pin "1") (pinfunction "3_1") (pintype "passive"))
      (node (ref "TNSY_19") (pin "1") (pinfunction "3_1") (pintype "passive"))
    )
    (net (code "21") (name "Net-(20-3)") (class "Default")
      (node (ref "20") (pin "1") (pinfunction "3_1") (pintype "passive"))
      (node (ref "TNSY_20") (pin "1") (pinfunction "3_1") (pintype "passive"))
    )
    (net (code "22") (name "Net-(21-3)") (class "Default")
      (node (ref "21") (pin "1") (pinfunction "3_1") (pintype "passive"))
      (node (ref "TNSY_21") (pin "1") (pinfunction "3_1") (pintype "passive"))
    )
    (net (code "23") (name "Net-(22-3)") (class "Default")
      (node (ref "22") (pin "1") (pinfunction "3_1") (pintype "passive"))
      (node (ref "TNSY_22") (pin "1") (pinfunction "3_1") (pintype "passive"))
    )
    (net (code "24") (name "Net-(23-3)") (class "Default")
      (node (ref "23") (pin "1") (pinfunction "3_1") (pintype "passive"))
      (node (ref "TNSY_23") (pin "1") (pinfunction "3_1") (pintype "passive"))
    )
    (net (code "25") (name "Net-(AVDDIO-3)") (class "Default")
      (node (ref "AVDDIO") (pin "1") (pinfunction "3_1") (pintype "passive"))
      (node (ref "AVDDIO1") (pin "1") (pinfunction "3_1") (pintype "passive"))
      (node (ref "D3") (pin "C") (pinfunction "C_C") (pintype "passive"))
      (node (ref "R21") (pin "1") (pinfunction "1_1") (pintype "passive"))
    )
    (net (code "26") (name "Net-(AVSSIO-3)") (class "Default")
      (node (ref "AVSSIO") (pin "1") (pinfunction "3_1") (pintype "passive"))
      (node (ref "AVSSIO1") (pin "1") (pinfunction "3_1") (pintype "passive"))
      (node (ref "D2") (pin "A") (pinfunction "A_A") (pintype "passive"))
      (node (ref "R22") (pin "1") (pinfunction "1_1") (pintype "passive"))
    )
    (net (code "27") (name "Net-(D4-PadC)") (class "Default")
      (node (ref "D4") (pin "C") (pinfunction "C_C") (pintype "passive"))
      (node (ref "IC1") (pin "1") (pinfunction "1_1") (pintype "passive"))
      (node (ref "R23") (pin "2") (pinfunction "2_2") (pintype "passive"))
    )
    (net (code "28") (name "Net-(D5-PadC)") (class "Default")
      (node (ref "D5") (pin "C") (pinfunction "C_C") (pintype "passive"))
      (node (ref "IC4") (pin "1") (pinfunction "1_1") (pintype "passive"))
      (node (ref "R27") (pin "2") (pinfunction "2_2") (pintype "passive"))
    )
    (net (code "29") (name "Net-(IC2-OUT)") (class "Default")
      (node (ref "D1") (pin "C") (pinfunction "C_C") (pintype "passive"))
      (node (ref "IC2") (pin "7") (pinfunction "OUT_7") (pintype "passive"))
      (node (ref "L3") (pin "1") (pinfunction "1_1") (pintype "passive"))
    )
    (net (code "30") (name "Net-(IC3A-O)") (class "Default")
      (node (ref "IC3") (pin "2") (pinfunction "O_2") (pintype "output"))
      (node (ref "IC3") (pin "3") (pinfunction "I_3") (pintype "input"))
    )
    (net (code "31") (name "Net-(IC3B-O)") (class "Default")
      (node (ref "IC3") (pin "4") (pinfunction "O_4") (pintype "output"))
      (node (ref "R25") (pin "2") (pinfunction "2_2") (pintype "passive"))
    )
    (net (code "32") (name "Net-(IC3E-O)") (class "Default")
      (node (ref "IC3") (pin "10") (pinfunction "O_10") (pintype "output"))
      (node (ref "IC3") (pin "13") (pinfunction "I_13") (pintype "input"))
    )
    (net (code "33") (name "Net-(IC3F-O)") (class "Default")
      (node (ref "IC3") (pin "12") (pinfunction "O_12") (pintype "output"))
      (node (ref "R29") (pin "2") (pinfunction "2_2") (pintype "passive"))
    )
    (net (code "34") (name "Net-(IO_0-3)") (class "Default")
      (node (ref "IO_0") (pin "1") (pinfunction "3_1") (pintype "passive"))
      (node (ref "R1") (pin "2") (pinfunction "2_2") (pintype "passive"))
    )
    (net (code "35") (name "Net-(IO_1-3)") (class "Default")
      (node (ref "IO_1") (pin "1") (pinfunction "3_1") (pintype "passive"))
      (node (ref "R2") (pin "2") (pinfunction "2_2") (pintype "passive"))
    )
    (net (code "36") (name "Net-(IO_2-3)") (class "Default")
      (node (ref "IO_2") (pin "1") (pinfunction "3_1") (pintype "passive"))
      (node (ref "R3") (pin "2") (pinfunction "2_2") (pintype "passive"))
    )
    (net (code "37") (name "Net-(IO_3-3)") (class "Default")
      (node (ref "IO_3") (pin "1") (pinfunction "3_1") (pintype "passive"))
      (node (ref "R4") (pin "2") (pinfunction "2_2") (pintype "passive"))
    )
    (net (code "38") (name "Net-(IO_4-3)") (class "Default")
      (node (ref "IO_4") (pin "1") (pinfunction "3_1") (pintype "passive"))
      (node (ref "R5") (pin "2") (pinfunction "2_2") (pintype "passive"))
    )
    (net (code "39") (name "Net-(IO_5-3)") (class "Default")
      (node (ref "IO_5") (pin "1") (pinfunction "3_1") (pintype "passive"))
      (node (ref "R6") (pin "2") (pinfunction "2_2") (pintype "passive"))
    )
    (net (code "40") (name "Net-(IO_6-3)") (class "Default")
      (node (ref "IO_6") (pin "1") (pinfunction "3_1") (pintype "passive"))
      (node (ref "R7") (pin "2") (pinfunction "2_2") (pintype "passive"))
    )
    (net (code "41") (name "Net-(IO_7-3)") (class "Default")
      (node (ref "IO_7") (pin "1") (pinfunction "3_1") (pintype "passive"))
      (node (ref "R8") (pin "2") (pinfunction "2_2") (pintype "passive"))
    )
    (net (code "42") (name "Net-(IO_8-3)") (class "Default")
      (node (ref "IO_8") (pin "1") (pinfunction "3_1") (pintype "passive"))
      (node (ref "R9") (pin "2") (pinfunction "2_2") (pintype "passive"))
    )
    (net (code "43") (name "Net-(IO_9-3)") (class "Default")
      (node (ref "IO_9") (pin "1") (pinfunction "3_1") (pintype "passive"))
      (node (ref "R10") (pin "2") (pinfunction "2_2") (pintype "passive"))
    )
    (net (code "44") (name "Net-(IO_10-3)") (class "Default")
      (node (ref "IO_10") (pin "1") (pinfunction "3_1") (pintype "passive"))
      (node (ref "R11") (pin "2") (pinfunction "2_2") (pintype "passive"))
    )
    (net (code "45") (name "Net-(IO_11-3)") (class "Default")
      (node (ref "IO_11") (pin "1") (pinfunction "3_1") (pintype "passive"))
      (node (ref "R12") (pin "2") (pinfunction "2_2") (pintype "passive"))
    )
    (net (code "46") (name "Net-(IO_12-3)") (class "Default")
      (node (ref "IO_12") (pin "1") (pinfunction "3_1") (pintype "passive"))
      (node (ref "R13") (pin "2") (pinfunction "2_2") (pintype "passive"))
    )
    (net (code "47") (name "Net-(IO_13-3)") (class "Default")
      (node (ref "IO_13") (pin "1") (pinfunction "3_1") (pintype "passive"))
      (node (ref "R14") (pin "2") (pinfunction "2_2") (pintype "passive"))
    )
    (net (code "48") (name "Net-(IO_14-3)") (class "Default")
      (node (ref "IO_14") (pin "1") (pinfunction "3_1") (pintype "passive"))
      (node (ref "R15") (pin "2") (pinfunction "2_2") (pintype "passive"))
    )
    (net (code "49") (name "Net-(IO_15-3)") (class "Default")
      (node (ref "IO_15") (pin "1") (pinfunction "3_1") (pintype "passive"))
      (node (ref "R16") (pin "2") (pinfunction "2_2") (pintype "passive"))
    )
    (net (code "50") (name "Net-(IO_16-3)") (class "Default")
      (node (ref "IO_16") (pin "1") (pinfunction "3_1") (pintype "passive"))
      (node (ref "R17") (pin "2") (pinfunction "2_2") (pintype "passive"))
    )
    (net (code "51") (name "Net-(IO_17-3)") (class "Default")
      (node (ref "IO_17") (pin "1") (pinfunction "3_1") (pintype "passive"))
      (node (ref "R18") (pin "2") (pinfunction "2_2") (pintype "passive"))
    )
    (net (code "52") (name "Net-(IO_18-3)") (class "Default")
      (node (ref "IO_18") (pin "1") (pinfunction "3_1") (pintype "passive"))
      (node (ref "R19") (pin "2") (pinfunction "2_2") (pintype "passive"))
    )
    (net (code "53") (name "Net-(IO_19-3)") (class "Default")
      (node (ref "IO_19") (pin "1") (pinfunction "3_1") (pintype "passive"))
      (node (ref "R20") (pin "2") (pinfunction "2_2") (pintype "passive"))
    )
    (net (code "54") (name "Net-(MIDI_IN4-3)") (class "Default")
      (node (ref "MIDI_IN4") (pin "1") (pinfunction "3_1") (pintype "passive"))
      (node (ref "R23") (pin "1") (pinfunction "1_1") (pintype "passive"))
    )
    (net (code "55") (name "Net-(MIDI_IN4_2-3)") (class "Default")
      (node (ref "MIDI_IN4_2") (pin "1") (pinfunction "3_1") (pintype "passive"))
      (node (ref "R27") (pin "1") (pinfunction "1_1") (pintype "passive"))
    )
    (net (code "56") (name "Net-(MIDI_IN5-3)") (class "Default")
      (node (ref "D4") (pin "A") (pinfunction "A_A") (pintype "passive"))
      (node (ref "IC1") (pin "2") (pinfunction "2_2") (pintype "passive"))
      (node (ref "MIDI_IN5") (pin "1") (pinfunction "3_1") (pintype "passive"))
    )
    (net (code "57") (name "Net-(MIDI_IN5_2-3)") (class "Default")
      (node (ref "D5") (pin "A") (pinfunction "A_A") (pintype "passive"))
      (node (ref "IC4") (pin "2") (pinfunction "2_2") (pintype "passive"))
      (node (ref "MIDI_IN5_2") (pin "1") (pinfunction "3_1") (pintype "passive"))
    )
    (net (code "58") (name "Net-(MIDI_OUT4-3)") (class "Default")
      (node (ref "MIDI_OUT4") (pin "1") (pinfunction "3_1") (pintype "passive"))
      (node (ref "R26") (pin "1") (pinfunction "1_1") (pintype "passive"))
    )
    (net (code "59") (name "Net-(MIDI_OUT4_2-3)") (class "Default")
      (node (ref "MIDI_OUT4_2") (pin "1") (pinfunction "3_1") (pintype "passive"))
      (node (ref "R30") (pin "1") (pinfunction "1_1") (pintype "passive"))
    )
    (net (code "60") (name "Net-(MIDI_OUT5-3)") (class "Default")
      (node (ref "MIDI_OUT5") (pin "1") (pinfunction "3_1") (pintype "passive"))
      (node (ref "R25") (pin "1") (pinfunction "1_1") (pintype "passive"))
    )
    (net (code "61") (name "Net-(MIDI_OUT5_2-3)") (class "Default")
      (node (ref "MIDI_OUT5_2") (pin "1") (pinfunction "3_1") (pintype "passive"))
      (node (ref "R29") (pin "1") (pinfunction "1_1") (pintype "passive"))
    )
    (net (code "62") (name "Net-(PIXI_0-3)") (class "Default")
      (node (ref "PIXI_0") (pin "1") (pinfunction "3_1") (pintype "passive"))
      (node (ref "R1") (pin "1") (pinfunction "1_1") (pintype "passive"))
    )
    (net (code "63") (name "Net-(PIXI_1-3)") (class "Default")
      (node (ref "PIXI_1") (pin "1") (pinfunction "3_1") (pintype "passive"))
      (node (ref "R2") (pin "1") (pinfunction "1_1") (pintype "passive"))
    )
    (net (code "64") (name "Net-(PIXI_2-3)") (class "Default")
      (node (ref "PIXI_2") (pin "1") (pinfunction "3_1") (pintype "passive"))
      (node (ref "R3") (pin "1") (pinfunction "1_1") (pintype "passive"))
    )
    (net (code "65") (name "Net-(PIXI_3-3)") (class "Default")
      (node (ref "PIXI_3") (pin "1") (pinfunction "3_1") (pintype "passive"))
      (node (ref "R4") (pin "1") (pinfunction "1_1") (pintype "passive"))
    )
    (net (code "66") (name "Net-(PIXI_4-3)") (class "Default")
      (node (ref "PIXI_4") (pin "1") (pinfunction "3_1") (pintype "passive"))
      (node (ref "R5") (pin "1") (pinfunction "1_1") (pintype "passive"))
    )
    (net (code "67") (name "Net-(PIXI_5-3)") (class "Default")
      (node (ref "PIXI_5") (pin "1") (pinfunction "3_1") (pintype "passive"))
      (node (ref "R6") (pin "1") (pinfunction "1_1") (pintype "passive"))
    )
    (net (code "68") (name "Net-(PIXI_6-3)") (class "Default")
      (node (ref "PIXI_6") (pin "1") (pinfunction "3_1") (pintype "passive"))
      (node (ref "R7") (pin "1") (pinfunction "1_1") (pintype "passive"))
    )
    (net (code "69") (name "Net-(PIXI_7-3)") (class "Default")
      (node (ref "PIXI_7") (pin "1") (pinfunction "3_1") (pintype "passive"))
      (node (ref "R8") (pin "1") (pinfunction "1_1") (pintype "passive"))
    )
    (net (code "70") (name "Net-(PIXI_8-3)") (class "Default")
      (node (ref "PIXI_8") (pin "1") (pinfunction "3_1") (pintype "passive"))
      (node (ref "R9") (pin "1") (pinfunction "1_1") (pintype "passive"))
    )
    (net (code "71") (name "Net-(PIXI_9-3)") (class "Default")
      (node (ref "PIXI_9") (pin "1") (pinfunction "3_1") (pintype "passive"))
      (node (ref "R10") (pin "1") (pinfunction "1_1") (pintype "passive"))
    )
    (net (code "72") (name "Net-(PIXI_10-3)") (class "Default")
      (node (ref "PIXI_10") (pin "1") (pinfunction "3_1") (pintype "passive"))
      (node (ref "R11") (pin "1") (pinfunction "1_1") (pintype "passive"))
    )
    (net (code "73") (name "Net-(PIXI_11-3)") (class "Default")
      (node (ref "PIXI_11") (pin "1") (pinfunction "3_1") (pintype "passive"))
      (node (ref "R12") (pin "1") (pinfunction "1_1") (pintype "passive"))
    )
    (net (code "74") (name "Net-(PIXI_12-3)") (class "Default")
      (node (ref "PIXI_12") (pin "1") (pinfunction "3_1") (pintype "passive"))
      (node (ref "R13") (pin "1") (pinfunction "1_1") (pintype "passive"))
    )
    (net (code "75") (name "Net-(PIXI_13-3)") (class "Default")
      (node (ref "PIXI_13") (pin "1") (pinfunction "3_1") (pintype "passive"))
      (node (ref "R14") (pin "1") (pinfunction "1_1") (pintype "passive"))
    )
    (net (code "76") (name "Net-(PIXI_14-3)") (class "Default")
      (node (ref "PIXI_14") (pin "1") (pinfunction "3_1") (pintype "passive"))
      (node (ref "R15") (pin "1") (pinfunction "1_1") (pintype "passive"))
    )
    (net (code "77") (name "Net-(PIXI_15-3)") (class "Default")
      (node (ref "PIXI_15") (pin "1") (pinfunction "3_1") (pintype "passive"))
      (node (ref "R16") (pin "1") (pinfunction "1_1") (pintype "passive"))
    )
    (net (code "78") (name "Net-(PIXI_16-3)") (class "Default")
      (node (ref "PIXI_16") (pin "1") (pinfunction "3_1") (pintype "passive"))
      (node (ref "R17") (pin "1") (pinfunction "1_1") (pintype "passive"))
    )
    (net (code "79") (name "Net-(PIXI_17-3)") (class "Default")
      (node (ref "PIXI_17") (pin "1") (pinfunction "3_1") (pintype "passive"))
      (node (ref "R18") (pin "1") (pinfunction "1_1") (pintype "passive"))
    )
    (net (code "80") (name "Net-(PIXI_18-3)") (class "Default")
      (node (ref "PIXI_18") (pin "1") (pinfunction "3_1") (pintype "passive"))
      (node (ref "R19") (pin "1") (pinfunction "1_1") (pintype "passive"))
    )
    (net (code "81") (name "Net-(PIXI_19-3)") (class "Default")
      (node (ref "PIXI_19") (pin "1") (pinfunction "3_1") (pintype "passive"))
      (node (ref "R20") (pin "1") (pinfunction "1_1") (pintype "passive"))
    )
    (net (code "82") (name "Net-(PIXI_CS-3)") (class "Default")
      (node (ref "PIXI_CS") (pin "1") (pinfunction "3_1") (pintype "passive"))
      (node (ref "TNSY_CS") (pin "1") (pinfunction "3_1") (pintype "passive"))
    )
    (net (code "83") (name "RX1") (class "Default")
      (node (ref "IC1") (pin "6") (pinfunction "6_6") (pintype "passive"))
      (node (ref "R24") (pin "1") (pinfunction "1_1") (pintype "passive"))
      (node (ref "TNSY_0") (pin "1") (pinfunction "3_1") (pintype "passive"))
    )
    (net (code "84") (name "RX2") (class "Default")
      (node (ref "IC4") (pin "6") (pinfunction "6_6") (pintype "passive"))
      (node (ref "R28") (pin "1") (pinfunction "1_1") (pintype "passive"))
      (node (ref "TNSY_7") (pin "1") (pinfunction "3_1") (pintype "passive"))
    )
    (net (code "85") (name "TX1") (class "Default")
      (node (ref "IC3") (pin "1") (pinfunction "I_1") (pintype "input"))
      (node (ref "TNSY_1") (pin "1") (pinfunction "3_1") (pintype "passive"))
    )
    (net (code "86") (name "TX2") (class "Default")
      (node (ref "IC3") (pin "11") (pinfunction "I_11") (pintype "input"))
      (node (ref "TNSY_8") (pin "1") (pinfunction "3_1") (pintype "passive"))
    )
    (net (code "87") (name "unconnected-(IC1-Pad3)") (class "Default")
      (node (ref "IC1") (pin "3") (pinfunction "3_3") (pintype "passive"))
    )
    (net (code "88") (name "unconnected-(IC1-Pad4)") (class "Default")
      (node (ref "IC1") (pin "4") (pinfunction "4_4") (pintype "passive"))
    )
    (net (code "89") (name "unconnected-(IC1-Pad5)") (class "Default")
      (node (ref "IC1") (pin "5") (pinfunction "5_5") (pintype "passive"))
    )
    (net (code "90") (name "unconnected-(IC4-Pad3)") (class "Default")
      (node (ref "IC4") (pin "3") (pinfunction "3_3") (pintype "passive"))
    )
    (net (code "91") (name "unconnected-(IC4-Pad4)") (class "Default")
      (node (ref "IC4") (pin "4") (pinfunction "4_4") (pintype "passive"))
    )
    (net (code "92") (name "unconnected-(IC4-Pad5)") (class "Default")
      (node (ref "IC4") (pin "5") (pinfunction "5_5") (pintype "passive"))
    )
    (net (code "93") (name "unconnected-(PIXI_INT-3-Pad1)") (class "Default")
      (node (ref "PIXI_INT") (pin "1") (pinfunction "3_1") (pintype "passive"))
    )
    (net (code "94") (name "unconnected-(PIXI_NC1-3-Pad1)") (class "Default")
      (node (ref "PIXI_NC1") (pin "1") (pinfunction "3_1") (pintype "passive"))
    )
    (net (code "95") (name "unconnected-(PIXI_NC2-3-Pad1)") (class "Default")
      (node (ref "PIXI_NC2") (pin "1") (pinfunction "3_1") (pintype "passive"))
    )
    (net (code "96") (name "unconnected-(PIXI_NC3-3-Pad1)") (class "Default")
      (node (ref "PIXI_NC3") (pin "1") (pinfunction "3_1") (pintype "passive"))
    )
    (net (code "97") (name "unconnected-(PIXI_NC4-3-Pad1)") (class "Default")
      (node (ref "PIXI_NC4") (pin "1") (pinfunction "3_1") (pintype "passive"))
    )
    (net (code "98") (name "unconnected-(PIXI_NC5-3-Pad1)") (class "Default")
      (node (ref "PIXI_NC5") (pin "1") (pinfunction "3_1") (pintype "passive"))
    )
    (net (code "99") (name "unconnected-(PIXI_NC6-3-Pad1)") (class "Default")
      (node (ref "PIXI_NC6") (pin "1") (pinfunction "3_1") (pintype "passive"))
    )
    (net (code "100") (name "unconnected-(TNSY_GND2-3-Pad1)") (class "Default")
      (node (ref "TNSY_GND2") (pin "1") (pinfunction "3_1") (pintype "passive"))
    )
  )
)
